# CurlingStoneSchematic.net
KiCad netlist of a schematic drawn in Altium Designer
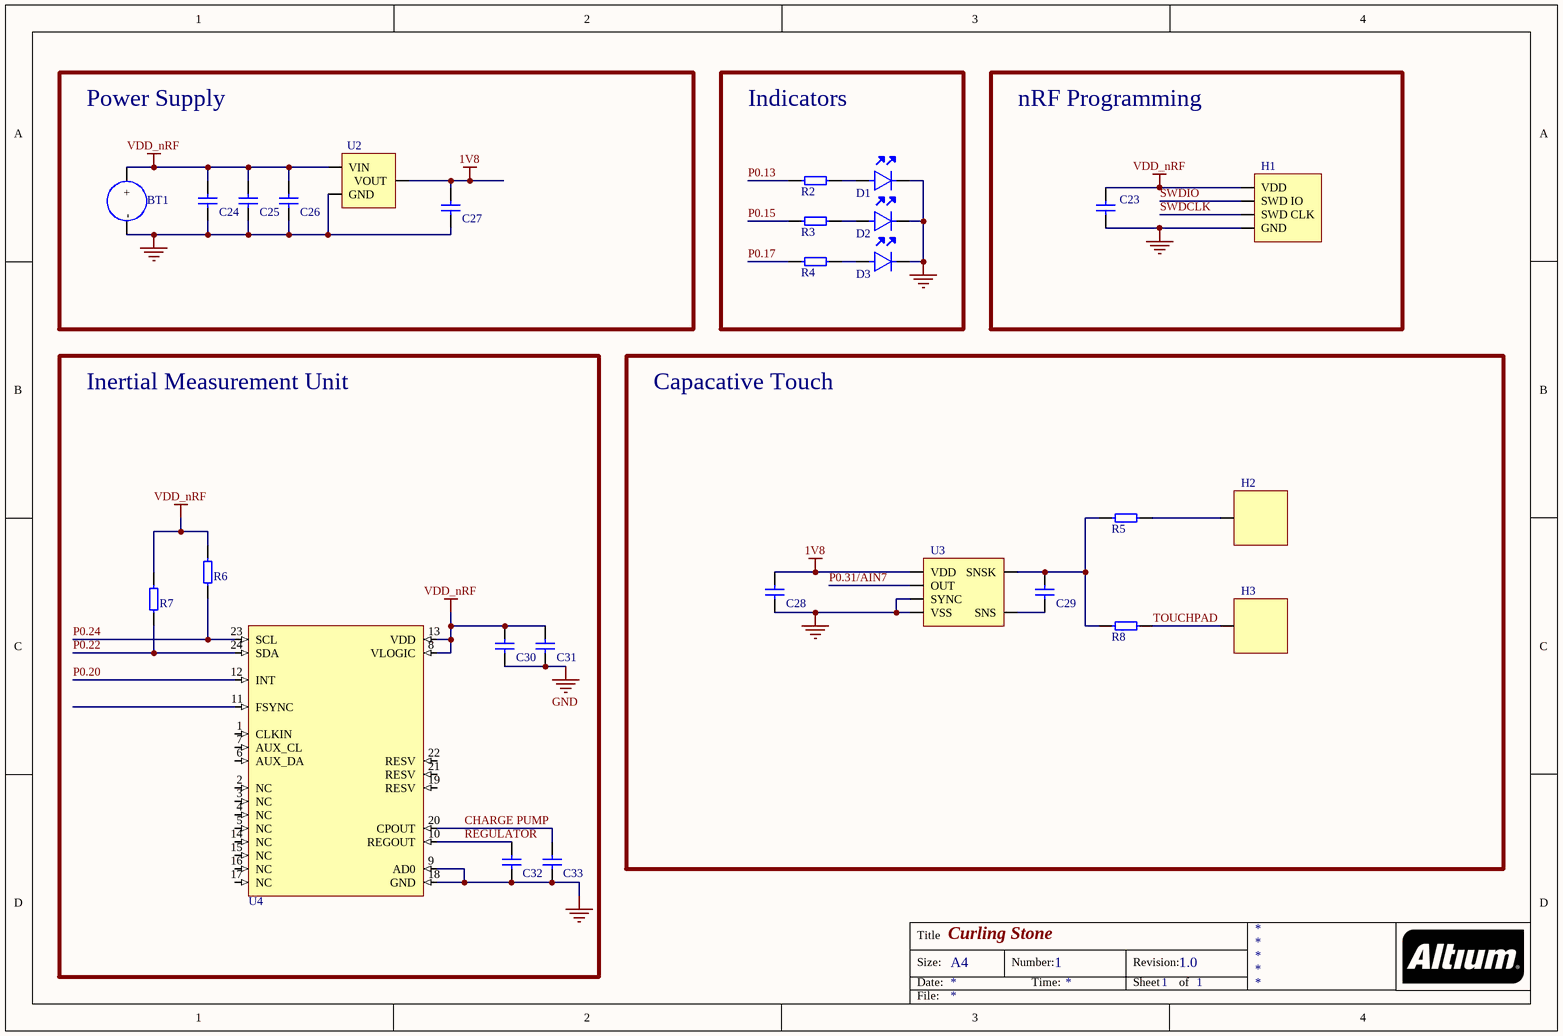
[diagram p0: CurlingStoneSchematic.SchDoc]

(export (version "E")
  (design (tool "Eeschema 10.0.6"))
  (components
    (comp (ref "BT1")
      (value "Battery Holder")
      (footprint "Battery Holder")
      (description "Battery Holder 1-Cell 20mm Size Tin Nickel SMT Mount T/R")
      (libsource (lib "CurlingStoneSchematicLibrary") (part "Battery Holder"))
    )
    (comp (ref "C23")
      (value "0603 Capacitor")
      (footprint "0603")
      (libsource (lib "CurlingStoneSchematicLibrary") (part "0603 Capacitor"))
    )
    (comp (ref "C24")
      (value "0603 Capacitor")
      (footprint "0603")
      (libsource (lib "CurlingStoneSchematicLibrary") (part "0603 Capacitor"))
    )
    (comp (ref "C25")
      (value "0603 Capacitor")
      (footprint "0603")
      (libsource (lib "CurlingStoneSchematicLibrary") (part "0603 Capacitor"))
    )
    (comp (ref "C26")
      (value "0603 Capacitor")
      (footprint "0603")
      (libsource (lib "CurlingStoneSchematicLibrary") (part "0603 Capacitor"))
    )
    (comp (ref "C27")
      (value "0603 Capacitor")
      (footprint "0603")
      (libsource (lib "CurlingStoneSchematicLibrary") (part "0603 Capacitor"))
    )
    (comp (ref "C28")
      (value "0603 Capacitor")
      (footprint "0603")
      (libsource (lib "CurlingStoneSchematicLibrary") (part "0603 Capacitor"))
    )
    (comp (ref "C29")
      (value "0603 Capacitor")
      (footprint "0603")
      (libsource (lib "CurlingStoneSchematicLibrary") (part "0603 Capacitor"))
    )
    (comp (ref "C30")
      (value "0603 Capacitor")
      (footprint "0603")
      (libsource (lib "CurlingStoneSchematicLibrary") (part "0603 Capacitor"))
    )
    (comp (ref "C31")
      (value "0603 Capacitor")
      (footprint "0603")
      (libsource (lib "CurlingStoneSchematicLibrary") (part "0603 Capacitor"))
    )
    (comp (ref "C32")
      (value "0603 Capacitor")
      (footprint "0603")
      (libsource (lib "CurlingStoneSchematicLibrary") (part "0603 Capacitor"))
    )
    (comp (ref "C33")
      (value "0603 Capacitor")
      (footprint "0603")
      (libsource (lib "CurlingStoneSchematicLibrary") (part "0603 Capacitor"))
    )
    (comp (ref "D1")
      (value "0603 LED")
      (footprint "0603 LED")
      (description "LED Uni-Color Green 574nm 2-Pin Chip LED T/R")
      (libsource (lib "CurlingStoneSchematicLibrary") (part "0603 LED"))
    )
    (comp (ref "D2")
      (value "0603 LED")
      (footprint "0603 LED")
      (description "LED Uni-Color Green 574nm 2-Pin Chip LED T/R")
      (libsource (lib "CurlingStoneSchematicLibrary") (part "0603 LED"))
    )
    (comp (ref "D3")
      (value "0603 LED")
      (footprint "0603 LED")
      (description "LED Uni-Color Green 574nm 2-Pin Chip LED T/R")
      (libsource (lib "CurlingStoneSchematicLibrary") (part "0603 LED"))
    )
    (comp (ref "H1")
      (value "4x1 Header")
      (footprint "4x1 HEADER TH")
      (libsource (lib "ElsysSchematicLibrary") (part "4x1 Header"))
    )
    (comp (ref "H2")
      (value "Electrode")
      (footprint "ELECTRODE EXTERNAL")
      (libsource (lib "CurlingStoneSchematicLibrary") (part "Electrode"))
    )
    (comp (ref "H3")
      (value "Electrode")
      (footprint "ELECTRODE INTERNAL")
      (libsource (lib "CurlingStoneSchematicLibrary") (part "Electrode"))
    )
    (comp (ref "R2")
      (value "0603 Resistor")
      (footprint "0603")
      (libsource (lib "CurlingStoneSchematicLibrary") (part "0603 Resistor"))
    )
    (comp (ref "R3")
      (value "0603 Resistor")
      (footprint "0603")
      (libsource (lib "CurlingStoneSchematicLibrary") (part "0603 Resistor"))
    )
    (comp (ref "R4")
      (value "0603 Resistor")
      (footprint "0603")
      (libsource (lib "CurlingStoneSchematicLibrary") (part "0603 Resistor"))
    )
    (comp (ref "R5")
      (value "0603 Resistor")
      (footprint "0603")
      (libsource (lib "CurlingStoneSchematicLibrary") (part "0603 Resistor"))
    )
    (comp (ref "R6")
      (value "0603 Resistor")
      (footprint "0603")
      (libsource (lib "CurlingStoneSchematicLibrary") (part "0603 Resistor"))
    )
    (comp (ref "R7")
      (value "0603 Resistor")
      (footprint "0603")
      (libsource (lib "CurlingStoneSchematicLibrary") (part "0603 Resistor"))
    )
    (comp (ref "R8")
      (value "0603 Resistor")
      (footprint "0603")
      (libsource (lib "CurlingStoneSchematicLibrary") (part "0603 Resistor"))
    )
    (comp (ref "U2")
      (value "MCP1700 1V8")
      (footprint "MCP1700 SOT-23")
      (libsource (lib "ElsysSchematicLibrary") (part "MCP1700 1V8"))
    )
    (comp (ref "U3")
      (value "Capacative Touch")
      (footprint "CAPACATIVE TOUCH")
      (description "Capacitive Touch Screen 1Keys 6-Pin SOT-23 Tape and Reel")
      (libsource (lib "CurlingStoneSchematicLibrary") (part "Capacative Touch"))
    )
    (comp (ref "U4")
      (value "MPU-6050")
      (footprint "MPU-6050")
      (description "INVENSENSE   MPU-6050   GYRO / ACCEL, 6-AXIS, I2C, QFN-24")
      (libsource (lib "CurlingStoneSchematicLibrary") (part "MPU-6050"))
    )
  )
  (nets
    (net (code "1") (name "/CHARGE PUMP") (class "Default")
      (node (ref "C33") (pin "2") (pintype "passive"))
      (node (ref "U4") (pin "20") (pinfunction "CPOUT_20") (pintype "input"))
    )
    (net (code "2") (name "/P0.13") (class "Default") (node (ref "R2") (pin "1") (pintype "passive")))
    (net (code "3") (name "/P0.15") (class "Default") (node (ref "R3") (pin "1") (pintype "passive")))
    (net (code "4") (name "/P0.17") (class "Default") (node (ref "R4") (pin "1") (pintype "passive")))
    (net (code "5") (name "/P0.20") (class "Default")
      (node (ref "U4") (pin "12") (pinfunction "INT_12") (pintype "input"))
    )
    (net (code "6") (name "/P0.22") (class "Default")
      (node (ref "R7") (pin "1") (pintype "passive"))
      (node (ref "U4") (pin "24") (pinfunction "SDA_24") (pintype "input"))
    )
    (net (code "7") (name "/P0.24") (class "Default")
      (node (ref "R6") (pin "1") (pintype "passive"))
      (node (ref "U4") (pin "23") (pinfunction "SCL_23") (pintype "input"))
    )
    (net (code "8") (name "/P0.31{slash}AIN7") (class "Default")
      (node (ref "U3") (pin "1") (pinfunction "OUT_1") (pintype "passive"))
    )
    (net (code "9") (name "/REGULATOR") (class "Default")
      (node (ref "C32") (pin "2") (pintype "passive"))
      (node (ref "U4") (pin "10") (pinfunction "REGOUT_10") (pintype "input"))
    )
    (net (code "10") (name "/SWDCLK") (class "Default")
      (node (ref "H1") (pin "4") (pinfunction "SWD_CLK_4") (pintype "passive"))
    )
    (net (code "11") (name "/SWDIO") (class "Default")
      (node (ref "H1") (pin "3") (pinfunction "SWD_IO_3") (pintype "passive"))
    )
    (net (code "12") (name "/TOUCHPAD") (class "Default")
      (node (ref "H3") (pin "1") (pinfunction "GND_1") (pintype "passive"))
      (node (ref "R8") (pin "2") (pintype "passive"))
    )
    (net (code "13") (name "1V8") (class "Default")
      (node (ref "C27") (pin "2") (pintype "passive"))
      (node (ref "C28") (pin "2") (pintype "passive"))
      (node (ref "U2") (pin "2") (pinfunction "VOUT_2") (pintype "passive"))
      (node (ref "U3") (pin "5") (pinfunction "VDD_5") (pintype "passive"))
    )
    (net (code "14") (name "GND") (class "Default")
      (node (ref "BT1") (pin "2") (pinfunction "-_2") (pintype "passive"))
      (node (ref "C23") (pin "1") (pintype "passive"))
      (node (ref "C24") (pin "1") (pintype "passive"))
      (node (ref "C25") (pin "1") (pintype "passive"))
      (node (ref "C26") (pin "1") (pintype "passive"))
      (node (ref "C27") (pin "1") (pintype "passive"))
      (node (ref "C28") (pin "1") (pintype "passive"))
      (node (ref "C30") (pin "1") (pintype "passive"))
      (node (ref "C31") (pin "1") (pintype "passive"))
      (node (ref "C32") (pin "1") (pintype "passive"))
      (node (ref "C33") (pin "1") (pintype "passive"))
      (node (ref "D1") (pin "2") (pintype "passive"))
      (node (ref "D2") (pin "2") (pintype "passive"))
      (node (ref "D3") (pin "2") (pintype "passive"))
      (node (ref "H1") (pin "2") (pinfunction "GND_2") (pintype "passive"))
      (node (ref "U2") (pin "1") (pinfunction "GND_1") (pintype "passive"))
      (node (ref "U3") (pin "2") (pinfunction "VSS_2") (pintype "passive"))
      (node (ref "U3") (pin "6") (pinfunction "SYNC_6") (pintype "passive"))
      (node (ref "U4") (pin "18") (pinfunction "GND_18") (pintype "input"))
      (node (ref "U4") (pin "9") (pinfunction "AD0_9") (pintype "input"))
    )
    (net (code "15") (name "Net-(D1-Pad1)") (class "Default")
      (node (ref "D1") (pin "1") (pintype "passive"))
      (node (ref "R2") (pin "2") (pintype "passive"))
    )
    (net (code "16") (name "Net-(D2-Pad1)") (class "Default")
      (node (ref "D2") (pin "1") (pintype "passive"))
      (node (ref "R3") (pin "2") (pintype "passive"))
    )
    (net (code "17") (name "Net-(D3-Pad1)") (class "Default")
      (node (ref "D3") (pin "1") (pintype "passive"))
      (node (ref "R4") (pin "2") (pintype "passive"))
    )
    (net (code "18") (name "Net-(H2-GND)") (class "Default")
      (node (ref "H2") (pin "1") (pinfunction "GND_1") (pintype "passive"))
      (node (ref "R5") (pin "2") (pintype "passive"))
    )
    (net (code "19") (name "Net-(U3-SNS)") (class "Default")
      (node (ref "C29") (pin "1") (pintype "passive"))
      (node (ref "U3") (pin "4") (pinfunction "SNS_4") (pintype "passive"))
    )
    (net (code "20") (name "Net-(U3-SNSK)") (class "Default")
      (node (ref "C29") (pin "2") (pintype "passive"))
      (node (ref "R5") (pin "1") (pintype "passive"))
      (node (ref "R8") (pin "1") (pintype "passive"))
      (node (ref "U3") (pin "3") (pinfunction "SNSK_3") (pintype "passive"))
    )
    (net (code "21") (name "VDD_nRF") (class "Default")
      (node (ref "BT1") (pin "1") (pinfunction "+_1") (pintype "passive"))
      (node (ref "C23") (pin "2") (pintype "passive"))
      (node (ref "C24") (pin "2") (pintype "passive"))
      (node (ref "C25") (pin "2") (pintype "passive"))
      (node (ref "C26") (pin "2") (pintype "passive"))
      (node (ref "C30") (pin "2") (pintype "passive"))
      (node (ref "C31") (pin "2") (pintype "passive"))
      (node (ref "H1") (pin "1") (pinfunction "VDD_1") (pintype "passive"))
      (node (ref "R6") (pin "2") (pintype "passive"))
      (node (ref "R7") (pin "2") (pintype "passive"))
      (node (ref "U2") (pin "3") (pinfunction "VIN_3") (pintype "passive"))
      (node (ref "U4") (pin "13") (pinfunction "VDD_13") (pintype "input"))
      (node (ref "U4") (pin "8") (pinfunction "VLOGIC_8") (pintype "input"))
    )
    (net (code "22") (name "unconnected-(U4-AUX_CL-Pad7)") (class "Default")
      (node (ref "U4") (pin "7") (pinfunction "AUX_CL_7") (pintype "input"))
    )
    (net (code "23") (name "unconnected-(U4-AUX_DA-Pad6)") (class "Default")
      (node (ref "U4") (pin "6") (pinfunction "AUX_DA_6") (pintype "input"))
    )
    (net (code "24") (name "unconnected-(U4-CLKIN-Pad1)") (class "Default")
      (node (ref "U4") (pin "1") (pinfunction "CLKIN_1") (pintype "input"))
    )
    (net (code "25") (name "unconnected-(U4-FSYNC-Pad11)") (class "Default")
      (node (ref "U4") (pin "11") (pinfunction "FSYNC_11") (pintype "input"))
    )
    (net (code "26") (name "unconnected-(U4-NC-Pad2)") (class "Default")
      (node (ref "U4") (pin "2") (pinfunction "NC_2") (pintype "input"))
    )
    (net (code "27") (name "unconnected-(U4-NC-Pad3)") (class "Default")
      (node (ref "U4") (pin "3") (pinfunction "NC_3") (pintype "input"))
    )
    (net (code "28") (name "unconnected-(U4-NC-Pad4)") (class "Default")
      (node (ref "U4") (pin "4") (pinfunction "NC_4") (pintype "input"))
    )
    (net (code "29") (name "unconnected-(U4-NC-Pad5)") (class "Default")
      (node (ref "U4") (pin "5") (pinfunction "NC_5") (pintype "input"))
    )
    (net (code "30") (name "unconnected-(U4-NC-Pad14)") (class "Default")
      (node (ref "U4") (pin "14") (pinfunction "NC_14") (pintype "input"))
    )
    (net (code "31") (name "unconnected-(U4-NC-Pad15)") (class "Default")
      (node (ref "U4") (pin "15") (pinfunction "NC_15") (pintype "input"))
    )
    (net (code "32") (name "unconnected-(U4-NC-Pad16)") (class "Default")
      (node (ref "U4") (pin "16") (pinfunction "NC_16") (pintype "input"))
    )
    (net (code "33") (name "unconnected-(U4-NC-Pad17)") (class "Default")
      (node (ref "U4") (pin "17") (pinfunction "NC_17") (pintype "input"))
    )
    (net (code "34") (name "unconnected-(U4-RESV-Pad19)") (class "Default")
      (node (ref "U4") (pin "19") (pinfunction "RESV_19") (pintype "input"))
    )
    (net (code "35") (name "unconnected-(U4-RESV-Pad21)") (class "Default")
      (node (ref "U4") (pin "21") (pinfunction "RESV_21") (pintype "input"))
    )
    (net (code "36") (name "unconnected-(U4-RESV-Pad22)") (class "Default")
      (node (ref "U4") (pin "22") (pinfunction "RESV_22") (pintype "input"))
    )
  )
)
